# design.net
KiCad netlist of a schematic drawn in EasyEDA Pro
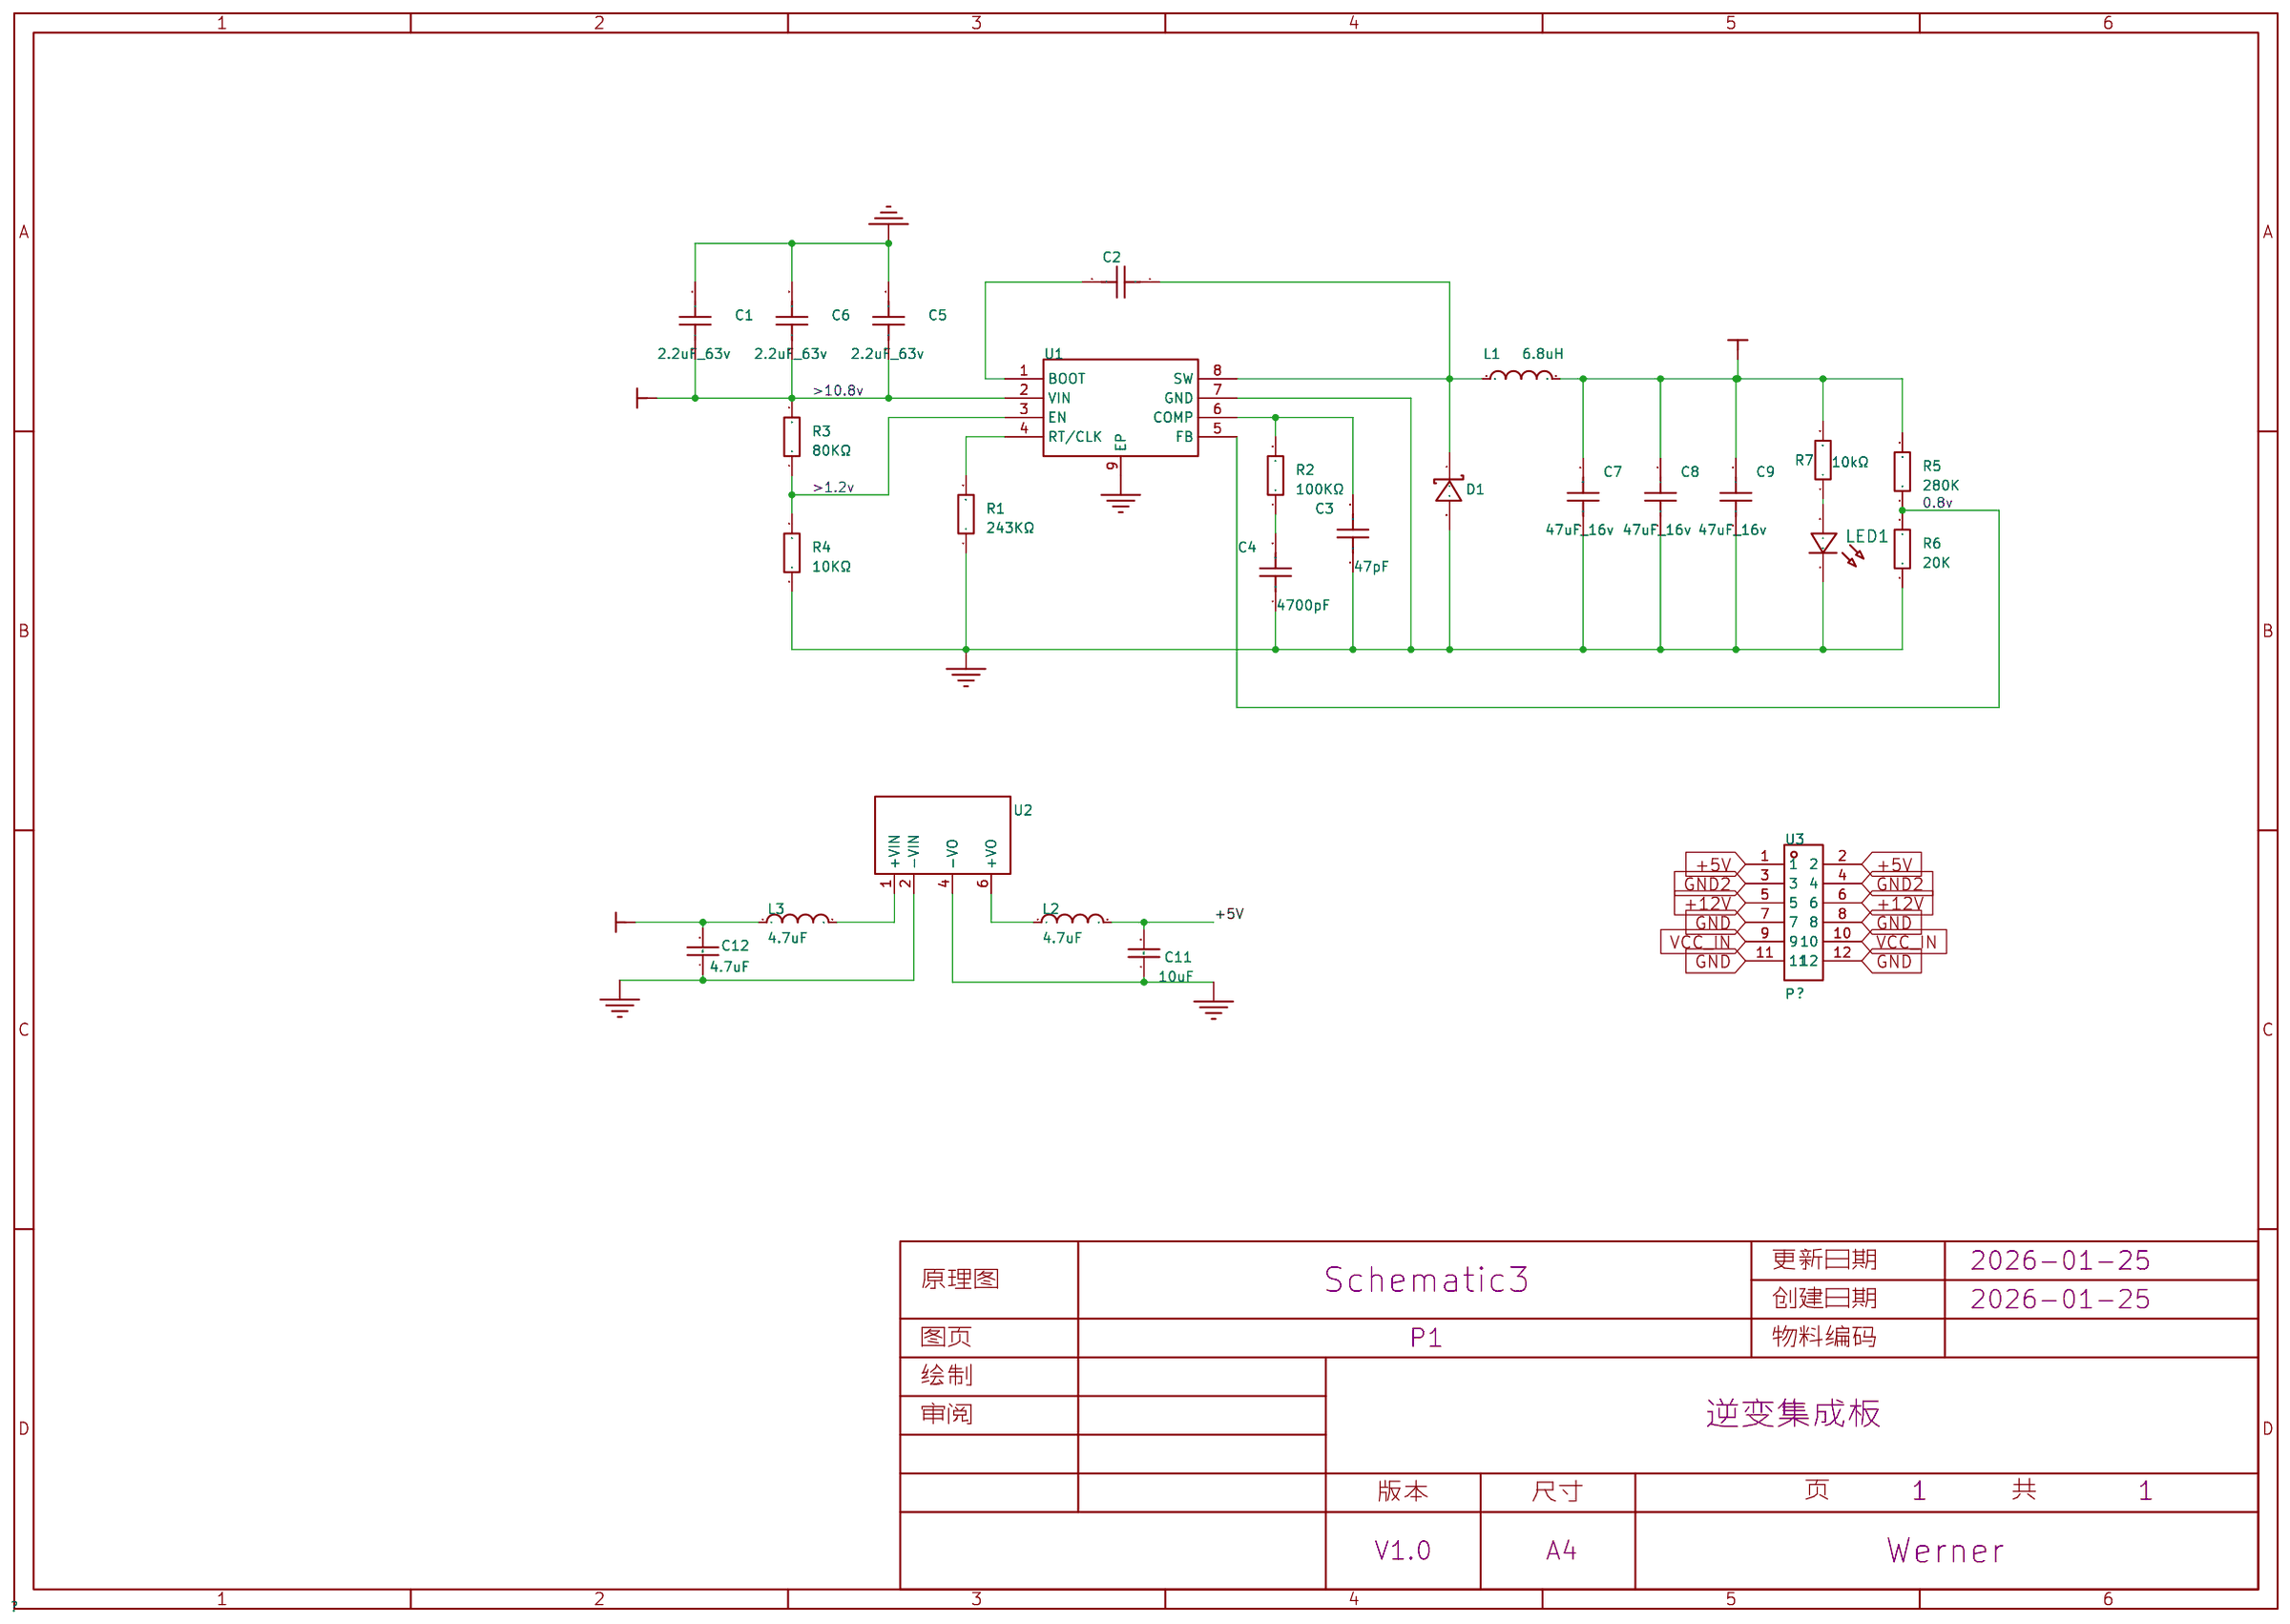
[diagram p0: schematic sheet]

(export (version "E")
  (design (tool "Eeschema 10.0.6"))
  (components
    (comp (ref "C1")
      (value "2.2uF_63v")
      (footprint "easyedapro:C0805")
      (libsource (lib "easyedapro") (part "Capacitance"))
    )
    (comp (ref "C2")
      (value "100nF")
      (footprint "easyedapro:C0805")
      (libsource (lib "easyedapro") (part "Capacitance"))
    )
    (comp (ref "C3")
      (value "47pF")
      (footprint "easyedapro:C0805")
      (libsource (lib "easyedapro") (part "Capacitance"))
    )
    (comp (ref "C4")
      (value "4700pF")
      (footprint "easyedapro:C0805")
      (libsource (lib "easyedapro") (part "Capacitance"))
    )
    (comp (ref "C5")
      (value "2.2uF_63v")
      (footprint "easyedapro:C0805")
      (libsource (lib "easyedapro") (part "Capacitance"))
    )
    (comp (ref "C6")
      (value "2.2uF_63v")
      (footprint "easyedapro:C0805")
      (libsource (lib "easyedapro") (part "Capacitance"))
    )
    (comp (ref "C7")
      (value "47uF_16v")
      (footprint "easyedapro:C0805")
      (libsource (lib "easyedapro") (part "Capacitance"))
    )
    (comp (ref "C8")
      (value "47uF_16v")
      (footprint "easyedapro:C0805")
      (libsource (lib "easyedapro") (part "Capacitance"))
    )
    (comp (ref "C9")
      (value "47uF_16v")
      (footprint "easyedapro:C0805")
      (libsource (lib "easyedapro") (part "Capacitance"))
    )
    (comp (ref "C11")
      (value "10uF")
      (footprint "easyedapro:C0603")
      (libsource (lib "easyedapro") (part "C0603"))
    )
    (comp (ref "C12")
      (value "4.7uF")
      (footprint "easyedapro:C0603")
      (libsource (lib "easyedapro") (part "C0603"))
    )
    (comp (ref "D1")
      (value "SS3200")
      (footprint "easyedapro:SMA_L4.3-W2.6-LS5.2-RD")
      (description "正向压降(Vf):950mV@3A;直流反向耐压(Vr):200V;平均整流电流(Io):3A;")
      (fields (field (name "Manufacturer") "MDD"))
      (libsource (lib "easyedapro") (part "SS3200_C65001"))
    )
    (comp (ref "L1")
      (value "6.8uH")
      (footprint "easyedapro:IND-SMD_L7.1-W6.6")
      (description "电感值:10uH;精度:±20%;饱和电流(Isat):4.5A;类型:一体成型电感;")
      (fields (field (name "Manufacturer Part") "D0630HP-100MT") (field (name "Manufacturer") "DEYAN(德砚电子)"))
      (libsource (lib "easyedapro") (part "D0630HP-100MT"))
    )
    (comp (ref "L2")
      (value "4.7uF")
      (footprint "easyedapro:IND-SMD_L4.9-W4.4_MAPM0420F")
      (description "电感值:10uH;精度:±20%;额定电流:1.5A;饱和电流(Isat):1.8A;")
      (fields (field (name "Manufacturer Part") "HA42-100MTP01") (field (name "Manufacturer") "FH(风华)"))
      (libsource (lib "easyedapro") (part "HA42-100MTP01"))
    )
    (comp (ref "L3")
      (value "4.7uF")
      (footprint "easyedapro:IND-SMD_L4.9-W4.4_MAPM0420F")
      (description "电感值:10uH;精度:±20%;额定电流:1.5A;饱和电流(Isat):1.8A;")
      (fields (field (name "Manufacturer Part") "HA42-100MTP01") (field (name "Manufacturer") "FH(风华)"))
      (libsource (lib "easyedapro") (part "HA42-100MTP01"))
    )
    (comp (ref "LED1")
      (value "~")
      (footprint "easyedapro:LED_0603")
      (libsource (lib "easyedapro") (part "LED_R"))
    )
    (comp (ref "R1")
      (value "243KΩ")
      (footprint "easyedapro:R0603")
      (libsource (lib "easyedapro") (part "电阻_1"))
    )
    (comp (ref "R2")
      (value "100KΩ")
      (footprint "easyedapro:R0603")
      (libsource (lib "easyedapro") (part "电阻_1"))
    )
    (comp (ref "R3")
      (value "80KΩ")
      (footprint "easyedapro:R0603")
      (libsource (lib "easyedapro") (part "电阻_1"))
    )
    (comp (ref "R4")
      (value "10KΩ")
      (footprint "easyedapro:R0603")
      (libsource (lib "easyedapro") (part "电阻_1"))
    )
    (comp (ref "R5")
      (value "280K")
      (footprint "easyedapro:R0603")
      (libsource (lib "easyedapro") (part "电阻_1"))
    )
    (comp (ref "R6")
      (value "20K")
      (footprint "easyedapro:R0603")
      (libsource (lib "easyedapro") (part "电阻_1"))
    )
    (comp (ref "R7")
      (value "10kΩ")
      (footprint "easyedapro:R0805")
      (description "电阻类型:厚膜电阻;阻值:5.1kΩ;精度:±1%;功率:125mW;最大工作电压:150V;温度系数:±100ppm/℃;")
      (fields
        (field (name "Manufacturer Part") "0805W8F5101T5E")
        (field (name "Manufacturer") "UNI-ROYAL(厚声)")
      )
      (libsource (lib "easyedapro") (part "0805W8F5101T5E"))
    )
    (comp (ref "U1")
      (value "TPS54560DDAR")
      (footprint "easyedapro:SOIC-8_L5.0-W4.0-P1.27-LS6.0-BL-EP2.0")
      (description "功能类型:降压型;输出类型:可调;工作电压:4.5V~60V;输出电压:800mV~58.8V;输出电流:5A;")
      (fields (field (name "Manufacturer") "TI(德州仪器)"))
      (libsource (lib "easyedapro") (part "TPS54560DDAR"))
    )
    (comp (ref "U2")
      (value "B1205S-2WR3")
      (footprint "easyedapro:PWRM-TH_4P-L19.7-W7.1_B1205S-2WR3")
      (fields (field (name "Manufacturer") "YLPTEC(易川)"))
      (libsource (lib "easyedapro") (part "B1205S-2WR3_C2992387"))
    )
    (comp (ref "U3") (value "P？") (libsource (lib "easyedapro") (part "辅助电源双层贴片排针6X2P")))
  )
  (nets
    (net (code "1") (name "+5V") (class "Default")
      (node (ref "C11") (pin "2") (pinfunction "2_2") (pintype "input"))
      (node (ref "L2") (pin "2") (pinfunction "2_2") (pintype "unspecified"))
      (node (ref "U3") (pin "1") (pinfunction "1_1") (pintype "unspecified"))
      (node (ref "U3") (pin "2") (pinfunction "2_2") (pintype "unspecified"))
    )
    (net (code "2") (name "+12V") (class "Default")
      (node (ref "C12") (pin "2") (pinfunction "2_2") (pintype "input"))
      (node (ref "C7") (pin "2") (pinfunction "2_2") (pintype "input"))
      (node (ref "C8") (pin "2") (pinfunction "2_2") (pintype "input"))
      (node (ref "C9") (pin "2") (pinfunction "2_2") (pintype "input"))
      (node (ref "L1") (pin "2") (pinfunction "2_2") (pintype "unspecified"))
      (node (ref "L3") (pin "1") (pinfunction "1_1") (pintype "unspecified"))
      (node (ref "R5") (pin "2") (pinfunction "2_2") (pintype "input"))
      (node (ref "R7") (pin "2") (pinfunction "2_2") (pintype "input"))
      (node (ref "U3") (pin "5") (pinfunction "5_5") (pintype "unspecified"))
      (node (ref "U3") (pin "6") (pinfunction "6_6") (pintype "unspecified"))
    )
    (net (code "3") (name "GND") (class "Default")
      (node (ref "C1") (pin "2") (pinfunction "2_2") (pintype "input"))
      (node (ref "C12") (pin "1") (pinfunction "1_1") (pintype "input"))
      (node (ref "C3") (pin "1") (pinfunction "1_1") (pintype "input"))
      (node (ref "C4") (pin "1") (pinfunction "1_1") (pintype "input"))
      (node (ref "C5") (pin "2") (pinfunction "2_2") (pintype "input"))
      (node (ref "C6") (pin "2") (pinfunction "2_2") (pintype "input"))
      (node (ref "C7") (pin "1") (pinfunction "1_1") (pintype "input"))
      (node (ref "C8") (pin "1") (pinfunction "1_1") (pintype "input"))
      (node (ref "C9") (pin "1") (pinfunction "1_1") (pintype "input"))
      (node (ref "D1") (pin "2") (pinfunction "A_2") (pintype "unspecified"))
      (node (ref "LED1") (pin "1") (pinfunction "C_1") (pintype "input"))
      (node (ref "R1") (pin "1") (pinfunction "1_1") (pintype "input"))
      (node (ref "R4") (pin "1") (pinfunction "1_1") (pintype "input"))
      (node (ref "R6") (pin "1") (pinfunction "1_1") (pintype "input"))
      (node (ref "U1") (pin "7") (pinfunction "GND_7") (pintype "unspecified"))
      (node (ref "U1") (pin "9") (pinfunction "EP_9") (pintype "unspecified"))
      (node (ref "U2") (pin "2") (pinfunction "-VIN_2") (pintype "unspecified"))
      (node (ref "U3") (pin "11") (pinfunction "11_11") (pintype "unspecified"))
      (node (ref "U3") (pin "12") (pinfunction "12_12") (pintype "unspecified"))
      (node (ref "U3") (pin "7") (pinfunction "7_7") (pintype "unspecified"))
      (node (ref "U3") (pin "8") (pinfunction "8_8") (pintype "unspecified"))
    )
    (net (code "4") (name "GND2") (class "Default")
      (node (ref "C11") (pin "1") (pinfunction "1_1") (pintype "input"))
      (node (ref "U2") (pin "4") (pinfunction "-VO_4") (pintype "unspecified"))
      (node (ref "U3") (pin "3") (pinfunction "3_3") (pintype "unspecified"))
      (node (ref "U3") (pin "4") (pinfunction "4_4") (pintype "unspecified"))
    )
    (net (code "5") (name "Net-(C4-Pad2)") (class "Default")
      (node (ref "C4") (pin "2") (pinfunction "2_2") (pintype "input"))
      (node (ref "R2") (pin "1") (pinfunction "1_1") (pintype "input"))
    )
    (net (code "6") (name "Net-(D1-K)") (class "Default")
      (node (ref "C2") (pin "1") (pinfunction "1_1") (pintype "input"))
      (node (ref "D1") (pin "1") (pinfunction "K_1") (pintype "unspecified"))
      (node (ref "L1") (pin "1") (pinfunction "1_1") (pintype "unspecified"))
      (node (ref "U1") (pin "8") (pinfunction "SW_8") (pintype "unspecified"))
    )
    (net (code "7") (name "Net-(LED1-A)") (class "Default")
      (node (ref "LED1") (pin "2") (pinfunction "A_2") (pintype "input"))
      (node (ref "R7") (pin "1") (pinfunction "1_1") (pintype "input"))
    )
    (net (code "8") (name "Net-(U1-BOOT)") (class "Default")
      (node (ref "C2") (pin "2") (pinfunction "2_2") (pintype "input"))
      (node (ref "U1") (pin "1") (pinfunction "BOOT_1") (pintype "unspecified"))
    )
    (net (code "9") (name "Net-(U1-COMP)") (class "Default")
      (node (ref "C3") (pin "2") (pinfunction "2_2") (pintype "input"))
      (node (ref "R2") (pin "2") (pinfunction "2_2") (pintype "input"))
      (node (ref "U1") (pin "6") (pinfunction "COMP_6") (pintype "unspecified"))
    )
    (net (code "10") (name "Net-(U1-EN)") (class "Default")
      (node (ref "R3") (pin "1") (pinfunction "1_1") (pintype "input"))
      (node (ref "R4") (pin "2") (pinfunction "2_2") (pintype "input"))
      (node (ref "U1") (pin "3") (pinfunction "EN_3") (pintype "unspecified"))
    )
    (net (code "11") (name "Net-(U1-FB)") (class "Default")
      (node (ref "R5") (pin "1") (pinfunction "1_1") (pintype "input"))
      (node (ref "R6") (pin "2") (pinfunction "2_2") (pintype "input"))
      (node (ref "U1") (pin "5") (pinfunction "FB_5") (pintype "unspecified"))
    )
    (net (code "12") (name "Net-(U1-RT{slash}CLK)") (class "Default")
      (node (ref "R1") (pin "2") (pinfunction "2_2") (pintype "input"))
      (node (ref "U1") (pin "4") (pinfunction "RT/CLK_4") (pintype "unspecified"))
    )
    (net (code "13") (name "Net-(U2-+VIN)") (class "Default")
      (node (ref "L3") (pin "2") (pinfunction "2_2") (pintype "unspecified"))
      (node (ref "U2") (pin "1") (pinfunction "+VIN_1") (pintype "unspecified"))
    )
    (net (code "14") (name "Net-(U2-+VO)") (class "Default")
      (node (ref "L2") (pin "1") (pinfunction "1_1") (pintype "unspecified"))
      (node (ref "U2") (pin "6") (pinfunction "+VO_6") (pintype "unspecified"))
    )
    (net (code "15") (name "VCC_IN") (class "Default")
      (node (ref "C1") (pin "1") (pinfunction "1_1") (pintype "input"))
      (node (ref "C5") (pin "1") (pinfunction "1_1") (pintype "input"))
      (node (ref "C6") (pin "1") (pinfunction "1_1") (pintype "input"))
      (node (ref "R3") (pin "2") (pinfunction "2_2") (pintype "input"))
      (node (ref "U1") (pin "2") (pinfunction "VIN_2") (pintype "unspecified"))
      (node (ref "U3") (pin "10") (pinfunction "10_10") (pintype "unspecified"))
      (node (ref "U3") (pin "9") (pinfunction "9_9") (pintype "unspecified"))
    )
  )
)
